# Day_light_emulate_for_birds_unrouted.net
KiCad netlist of a schematic drawn in EAGLE
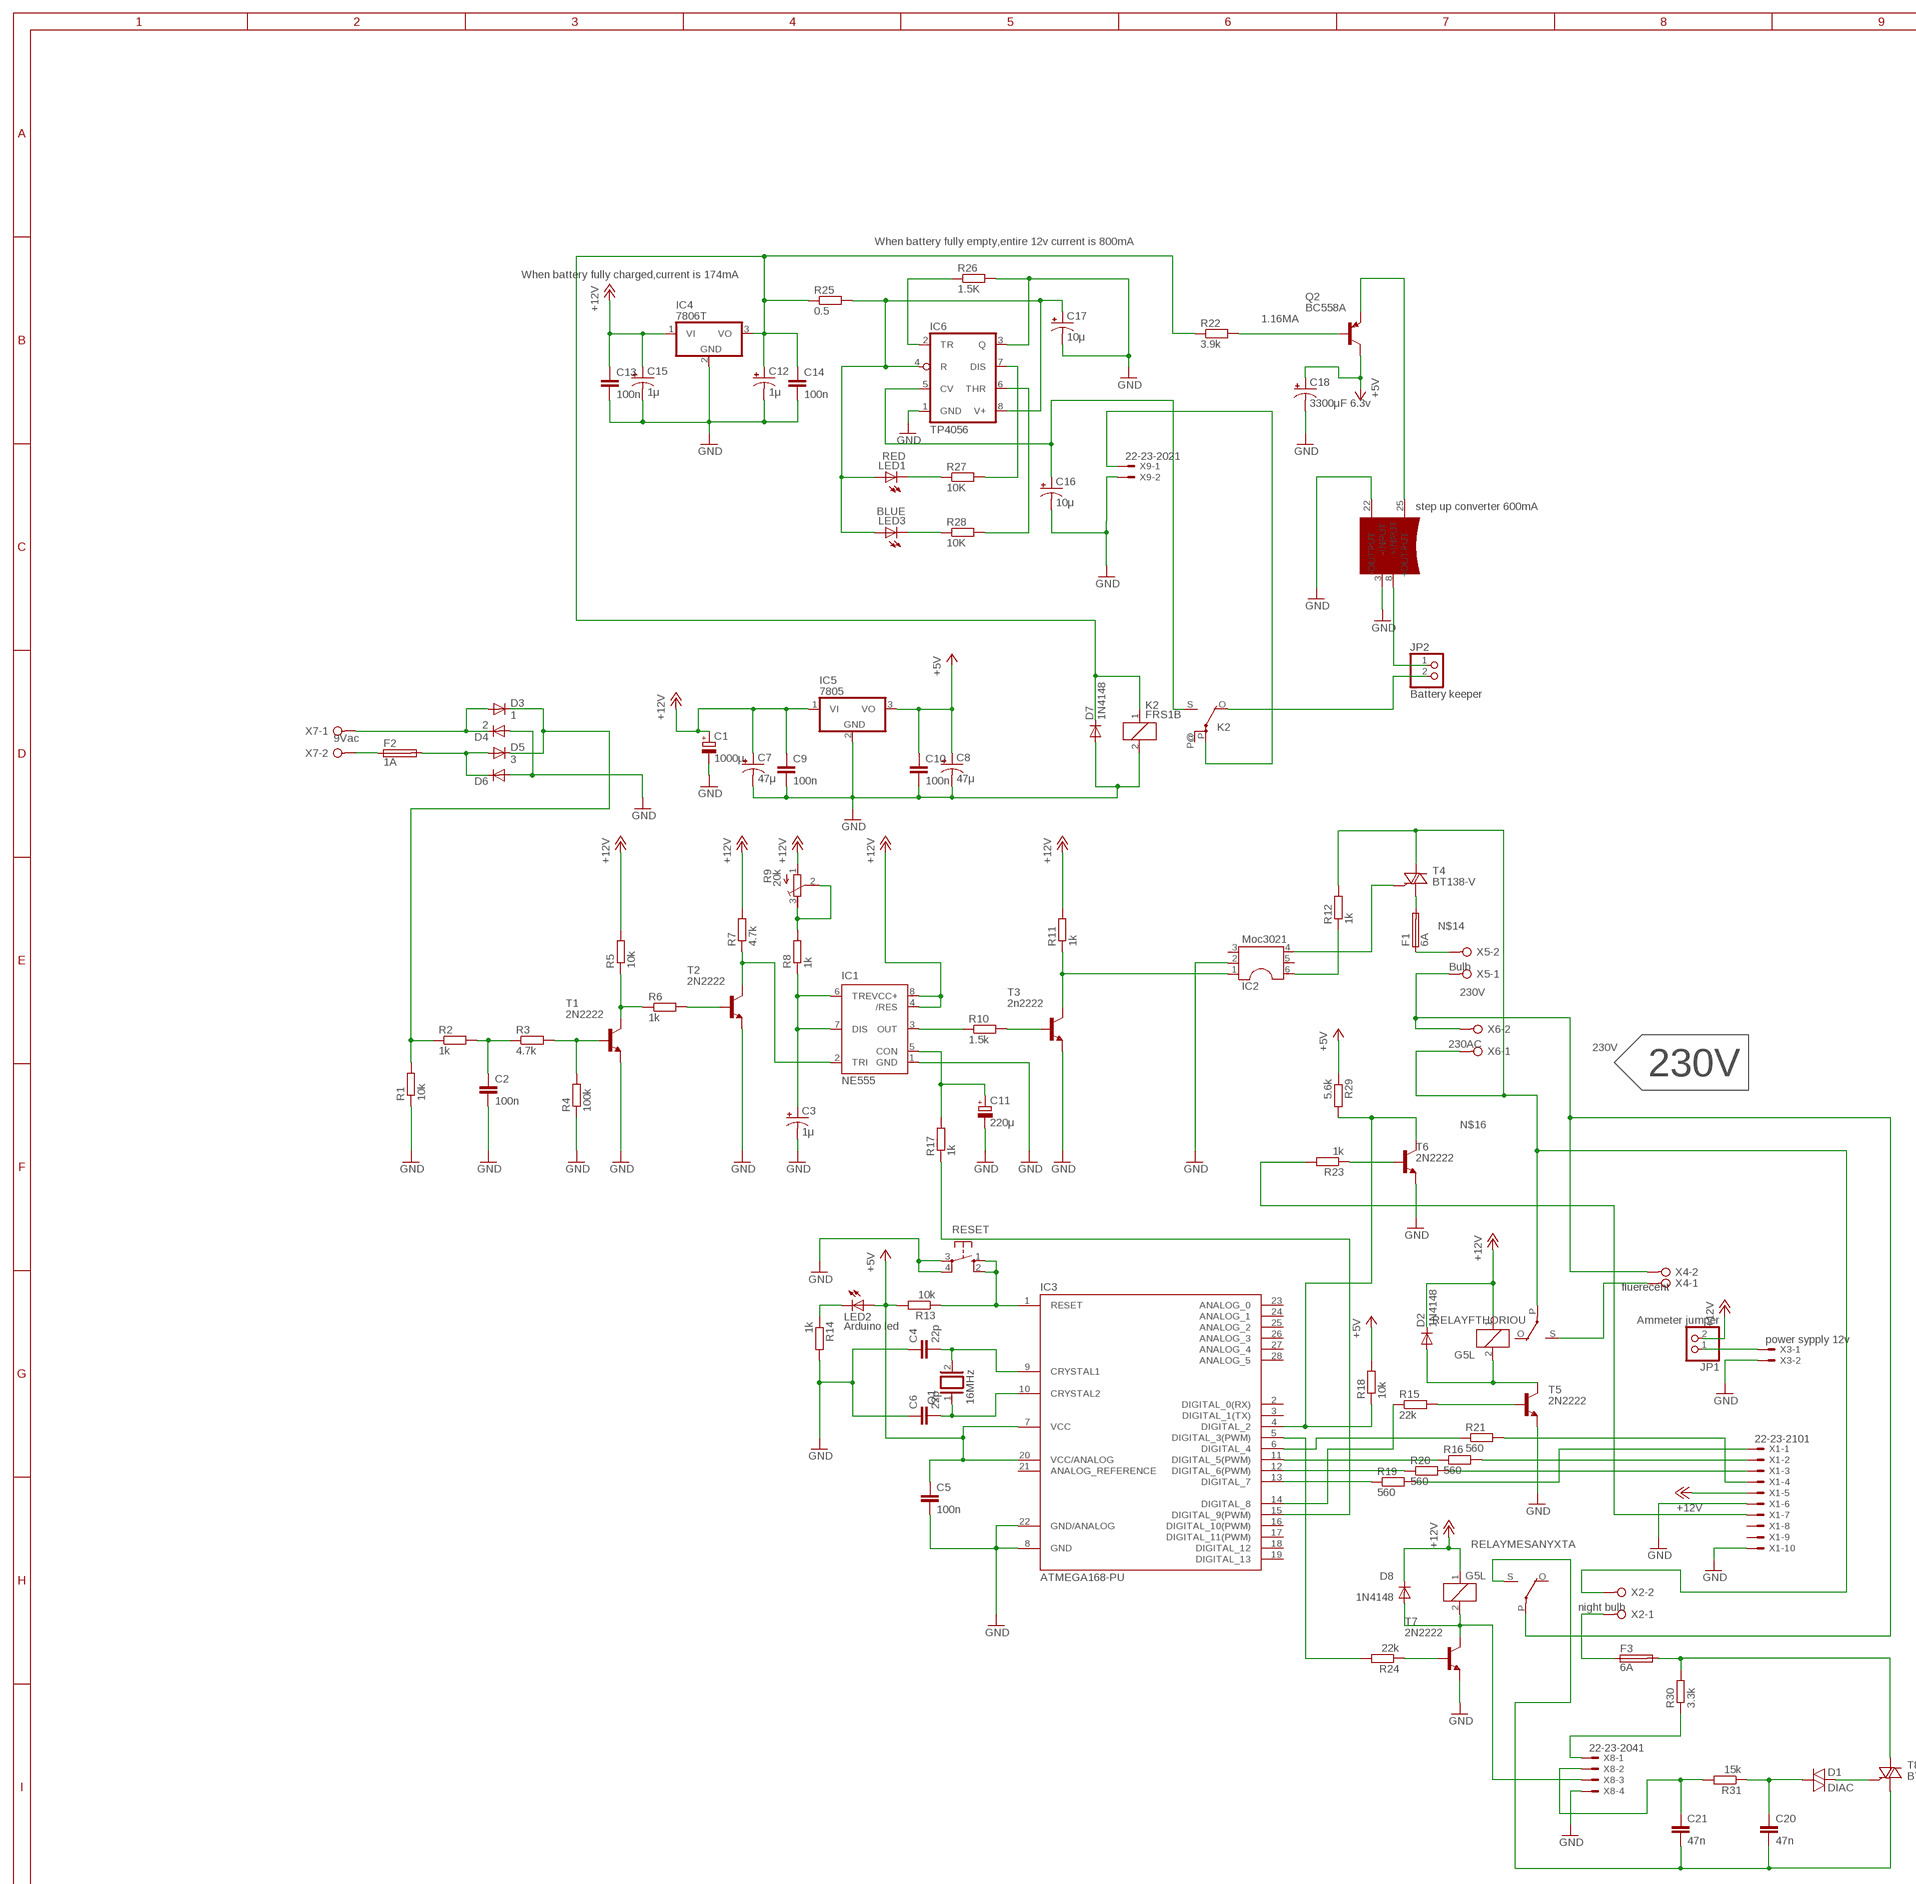
[diagram p0: schematic, sheet 1, part 1 of 2]
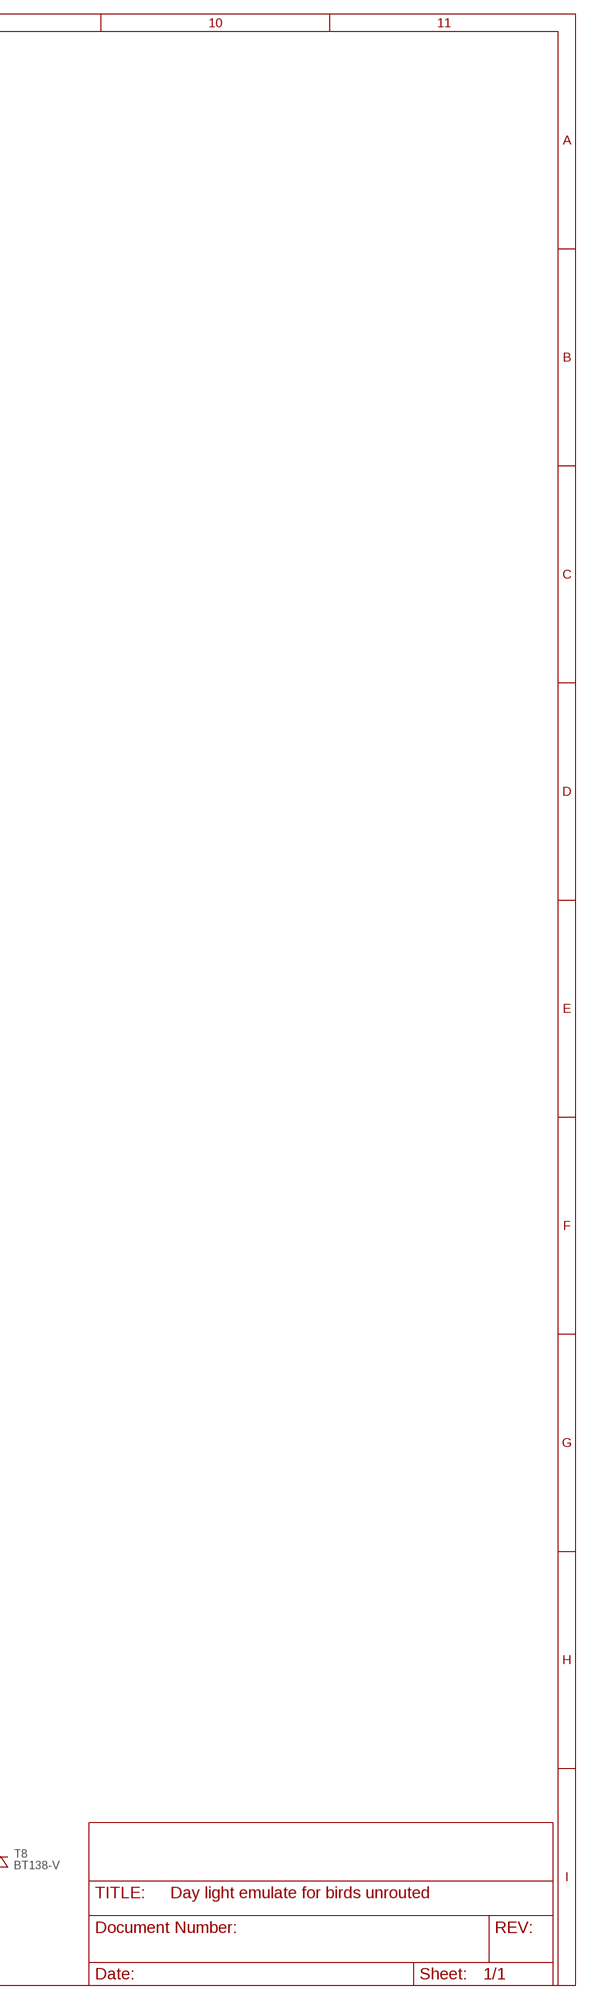
[diagram p1: schematic, sheet 1, part 2 of 2]

(export (version "E")
  (design (tool "Eeschema 10.0.6"))
  (components
    (comp (ref "C1")
      (value "1000μ")
      (footprint "eagle-import:E5-13")
      (libsource (lib "eagle-import") (part "CPOL-EUE5-13"))
    )
    (comp (ref "C2")
      (value "100n")
      (footprint "eagle-import:C025-030X050")
      (libsource (lib "eagle-import") (part "C-EU025-030X050"))
    )
    (comp (ref "C3")
      (value "1μ")
      (footprint "eagle-import:E2-4")
      (libsource (lib "eagle-import") (part "CPOL-USE2-4"))
    )
    (comp (ref "C4")
      (value "22p")
      (footprint "eagle-import:C025-030X050")
      (libsource (lib "eagle-import") (part "C-EU025-030X050"))
    )
    (comp (ref "C5")
      (value "100n")
      (footprint "eagle-import:C025-030X050")
      (libsource (lib "eagle-import") (part "C-EU025-030X050"))
    )
    (comp (ref "C6")
      (value "22p")
      (footprint "eagle-import:C025-030X050")
      (libsource (lib "eagle-import") (part "C-EU025-030X050"))
    )
    (comp (ref "C7")
      (value "47μ")
      (footprint "eagle-import:E2-4")
      (libsource (lib "eagle-import") (part "CPOL-USE2-4"))
    )
    (comp (ref "C8")
      (value "47μ")
      (footprint "eagle-import:E2-4")
      (libsource (lib "eagle-import") (part "CPOL-USE2-4"))
    )
    (comp (ref "C9")
      (value "100n")
      (footprint "eagle-import:C025-030X050")
      (libsource (lib "eagle-import") (part "C-EU025-030X050"))
    )
    (comp (ref "C10")
      (value "100n")
      (footprint "eagle-import:C025-030X050")
      (libsource (lib "eagle-import") (part "C-EU025-030X050"))
    )
    (comp (ref "C11")
      (value "220μ")
      (footprint "eagle-import:E5-10,5")
      (libsource (lib "eagle-import") (part "CPOL-EUE5-10.5"))
    )
    (comp (ref "C12")
      (value "1μ")
      (footprint "eagle-import:E2-4")
      (libsource (lib "eagle-import") (part "CPOL-USE2-4"))
    )
    (comp (ref "C13")
      (value "100n")
      (footprint "eagle-import:C025-030X050")
      (libsource (lib "eagle-import") (part "C-EU025-030X050"))
    )
    (comp (ref "C14")
      (value "100n")
      (footprint "eagle-import:C025-030X050")
      (libsource (lib "eagle-import") (part "C-EU025-030X050"))
    )
    (comp (ref "C15")
      (value "1μ")
      (footprint "eagle-import:E2-4")
      (libsource (lib "eagle-import") (part "CPOL-USE2-4"))
    )
    (comp (ref "C16")
      (value "10μ")
      (footprint "eagle-import:E2-4")
      (libsource (lib "eagle-import") (part "CPOL-USE2-4"))
    )
    (comp (ref "C17")
      (value "10μ")
      (footprint "eagle-import:E2-4")
      (libsource (lib "eagle-import") (part "CPOL-USE2-4"))
    )
    (comp (ref "C18")
      (value "3300μF 6.3v")
      (footprint "eagle-import:E5-6")
      (libsource (lib "eagle-import") (part "CPOL-USE5-6"))
    )
    (comp (ref "C20")
      (value "47n")
      (footprint "eagle-import:C025-030X050")
      (libsource (lib "eagle-import") (part "C-EU025-030X050"))
    )
    (comp (ref "C21")
      (value "47n")
      (footprint "eagle-import:C025-030X050")
      (libsource (lib "eagle-import") (part "C-EU025-030X050"))
    )
    (comp (ref "D1")
      (value "DIAC")
      (footprint "eagle-import:GT32")
      (libsource (lib "eagle-import") (part "DIAC-GT32"))
    )
    (comp (ref "D2")
      (value "1N4148")
      (footprint "eagle-import:DO35-10")
      (libsource (lib "eagle-import") (part "1N4148"))
    )
    (comp (ref "D3")
      (value "1")
      (footprint "eagle-import:DO41-10")
      (libsource (lib "eagle-import") (part "1N4004"))
    )
    (comp (ref "D4")
      (value "2")
      (footprint "eagle-import:DO41-10")
      (libsource (lib "eagle-import") (part "1N4004"))
    )
    (comp (ref "D5")
      (value "3")
      (footprint "eagle-import:DO41-10")
      (libsource (lib "eagle-import") (part "1N4004"))
    )
    (comp (ref "D6")
      (value "1N4004")
      (footprint "eagle-import:DO41-10")
      (libsource (lib "eagle-import") (part "1N4004"))
    )
    (comp (ref "D7")
      (value "1N4148")
      (footprint "eagle-import:DO35-10")
      (libsource (lib "eagle-import") (part "1N4148"))
    )
    (comp (ref "D8")
      (value "1N4148")
      (footprint "eagle-import:DO35-10")
      (libsource (lib "eagle-import") (part "1N4148"))
    )
    (comp (ref "F1")
      (value "6A")
      (footprint "eagle-import:SHK20L")
      (libsource (lib "eagle-import") (part "FUSESHK20L"))
    )
    (comp (ref "F2")
      (value "1A")
      (footprint "eagle-import:SHK20L")
      (libsource (lib "eagle-import") (part "FUSESHK20L"))
    )
    (comp (ref "F3")
      (value "6A")
      (footprint "eagle-import:SHK20L")
      (libsource (lib "eagle-import") (part "FUSESHK20L"))
    )
    (comp (ref "IC1")
      (value "NE555")
      (footprint "eagle-import:DIL-08")
      (libsource (lib "eagle-import") (part "NE555"))
    )
    (comp (ref "IC2")
      (value "Moc3021")
      (footprint "eagle-import:DIL06")
      (libsource (lib "eagle-import") (part "DIL6"))
    )
    (comp (ref "IC3")
      (value "ATMEGA168-PU")
      (footprint "eagle-import:DIL28-3")
      (libsource (lib "eagle-import") (part "ATMEGA168-PU"))
    )
    (comp (ref "IC4")
      (value "7806T")
      (footprint "eagle-import:TO220H")
      (libsource (lib "eagle-import") (part "78T06"))
    )
    (comp (ref "IC5")
      (value "7805")
      (footprint "eagle-import:TO220V")
      (libsource (lib "eagle-import") (part "78TV05"))
    )
    (comp (ref "IC6")
      (value "TP4056")
      (footprint "eagle-import:SO08")
      (libsource (lib "eagle-import") (part "555DLM"))
    )
    (comp (ref "JP1")
      (value "Ammeter jumper")
      (footprint "eagle-import:1X02")
      (libsource (lib "eagle-import") (part "PINHD-1X2"))
    )
    (comp (ref "JP2")
      (value "Battery keeper")
      (footprint "eagle-import:1X02")
      (libsource (lib "eagle-import") (part "PINHD-1X2"))
    )
    (comp (ref "K2")
      (value "FRS1B")
      (footprint "eagle-import:FRS1B")
      (libsource (lib "eagle-import") (part "FRS1B"))
    )
    (comp (ref "LED1")
      (value "RED")
      (footprint "eagle-import:LED3MM")
      (libsource (lib "eagle-import") (part "LED3MM"))
    )
    (comp (ref "LED2")
      (value "Arduino led")
      (footprint "eagle-import:LED3MM")
      (libsource (lib "eagle-import") (part "led_LED3MM"))
    )
    (comp (ref "LED3")
      (value "BLUE")
      (footprint "eagle-import:LED3MM")
      (libsource (lib "eagle-import") (part "LED3MM"))
    )
    (comp (ref "Q1")
      (value "16MHz")
      (footprint "eagle-import:QS")
      (libsource (lib "eagle-import") (part "XTAL/S"))
    )
    (comp (ref "Q2")
      (value "BC558A")
      (footprint "eagle-import:TO92-EBC")
      (libsource (lib "eagle-import") (part "BC558A"))
    )
    (comp (ref "R1")
      (value "10k")
      (footprint "eagle-import:0207_10")
      (libsource (lib "eagle-import") (part "R-EU_0207/10"))
    )
    (comp (ref "R2")
      (value "1k")
      (footprint "eagle-import:0207_10")
      (libsource (lib "eagle-import") (part "R-EU_0207/10"))
    )
    (comp (ref "R3")
      (value "4.7k")
      (footprint "eagle-import:0207_10")
      (libsource (lib "eagle-import") (part "R-EU_0207/10"))
    )
    (comp (ref "R4")
      (value "100k")
      (footprint "eagle-import:0207_10")
      (libsource (lib "eagle-import") (part "R-EU_0207/10"))
    )
    (comp (ref "R5")
      (value "10k")
      (footprint "eagle-import:0207_10")
      (libsource (lib "eagle-import") (part "R-EU_0207/10"))
    )
    (comp (ref "R6")
      (value "1k")
      (footprint "eagle-import:0207_10")
      (libsource (lib "eagle-import") (part "R-EU_0207/10"))
    )
    (comp (ref "R7")
      (value "4.7k")
      (footprint "eagle-import:0207_10")
      (libsource (lib "eagle-import") (part "R-EU_0207/10"))
    )
    (comp (ref "R8")
      (value "1k")
      (footprint "eagle-import:0207_10")
      (libsource (lib "eagle-import") (part "R-EU_0207/10"))
    )
    (comp (ref "R9")
      (value "20k")
      (footprint "eagle-import:RTRIM3339P")
      (libsource (lib "eagle-import") (part "R-TRIMM3339P"))
    )
    (comp (ref "R10")
      (value "1.5k")
      (footprint "eagle-import:0207_10")
      (libsource (lib "eagle-import") (part "R-EU_0207/10"))
    )
    (comp (ref "R11")
      (value "1k")
      (footprint "eagle-import:0207_10")
      (libsource (lib "eagle-import") (part "R-EU_0207/10"))
    )
    (comp (ref "R12")
      (value "1k")
      (footprint "eagle-import:0207_10")
      (libsource (lib "eagle-import") (part "R-EU_0207/10"))
    )
    (comp (ref "R13")
      (value "10k")
      (footprint "eagle-import:0207_10")
      (libsource (lib "eagle-import") (part "R-EU_0207/10"))
    )
    (comp (ref "R14")
      (value "1k")
      (footprint "eagle-import:0207_10")
      (libsource (lib "eagle-import") (part "R-EU_0207/10"))
    )
    (comp (ref "R15")
      (value "22k")
      (footprint "eagle-import:0207_10")
      (libsource (lib "eagle-import") (part "R-EU_0207/10"))
    )
    (comp (ref "R16")
      (value "560")
      (footprint "eagle-import:0207_10")
      (libsource (lib "eagle-import") (part "R-EU_0207/10"))
    )
    (comp (ref "R17")
      (value "1k")
      (footprint "eagle-import:0207_10")
      (libsource (lib "eagle-import") (part "R-EU_0207/10"))
    )
    (comp (ref "R18")
      (value "10k")
      (footprint "eagle-import:0207_10")
      (libsource (lib "eagle-import") (part "R-EU_0207/10"))
    )
    (comp (ref "R19")
      (value "560")
      (footprint "eagle-import:0207_10")
      (libsource (lib "eagle-import") (part "R-EU_0207/10"))
    )
    (comp (ref "R20")
      (value "560")
      (footprint "eagle-import:0207_10")
      (libsource (lib "eagle-import") (part "R-EU_0207/10"))
    )
    (comp (ref "R21")
      (value "560")
      (footprint "eagle-import:0207_10")
      (libsource (lib "eagle-import") (part "R-EU_0207/10"))
    )
    (comp (ref "R22")
      (value "3.9k")
      (footprint "eagle-import:0207_10")
      (libsource (lib "eagle-import") (part "R-EU_0207/10"))
    )
    (comp (ref "R23")
      (value "1k")
      (footprint "eagle-import:0207_10")
      (libsource (lib "eagle-import") (part "R-EU_0207/10"))
    )
    (comp (ref "R24")
      (value "22k")
      (footprint "eagle-import:0207_10")
      (libsource (lib "eagle-import") (part "R-EU_0207/10"))
    )
    (comp (ref "R25")
      (value "0.5")
      (footprint "eagle-import:0207_10")
      (libsource (lib "eagle-import") (part "R-EU_0207/10"))
    )
    (comp (ref "R26")
      (value "1.5K")
      (footprint "eagle-import:0207_10")
      (fields (field (name "CURRENT") "When battery fully empty,entire 12v current is 800mA"))
      (libsource (lib "eagle-import") (part "R-EU_0207/10"))
    )
    (comp (ref "R27")
      (value "10K")
      (footprint "eagle-import:0207_10")
      (libsource (lib "eagle-import") (part "R-EU_0207/10"))
    )
    (comp (ref "R28")
      (value "10K")
      (footprint "eagle-import:0207_10")
      (libsource (lib "eagle-import") (part "R-EU_0207/10"))
    )
    (comp (ref "R29")
      (value "5.6k")
      (footprint "eagle-import:0207_10")
      (libsource (lib "eagle-import") (part "R-EU_0207/10"))
    )
    (comp (ref "R30")
      (value "3.3k")
      (footprint "eagle-import:0207_10")
      (libsource (lib "eagle-import") (part "R-EU_0207/10"))
    )
    (comp (ref "R31")
      (value "15k")
      (footprint "eagle-import:0207_10")
      (libsource (lib "eagle-import") (part "R-EU_0207/10"))
    )
    (comp (ref "RELAYFTHORIOU")
      (value "G5L")
      (footprint "eagle-import:G5LE")
      (libsource (lib "eagle-import") (part "G5L"))
    )
    (comp (ref "RELAYMESANYXTA")
      (value "G5L")
      (footprint "eagle-import:G5LE")
      (libsource (lib "eagle-import") (part "G5L"))
    )
    (comp (ref "RESET")
      (value "10-XX")
      (footprint "eagle-import:B3F-10XX")
      (libsource (lib "eagle-import") (part "10-XX"))
    )
    (comp (ref "STEPUP1")
      (value "steup converter 600mA")
      (footprint "eagle-import:STEPUP_CONVERTER_600MA")
      (fields (field (name "STEPUP") "step up converter 600mA"))
      (libsource (lib "eagle-import") (part "STEP_UP_CONVERTER_600MA"))
    )
    (comp (ref "T1")
      (value "2N2222")
      (footprint "eagle-import:TO18")
      (libsource (lib "eagle-import") (part "2N2222"))
    )
    (comp (ref "T2")
      (value "2N2222")
      (footprint "eagle-import:TO18")
      (libsource (lib "eagle-import") (part "2N2222"))
    )
    (comp (ref "T3")
      (value "2n2222")
      (footprint "eagle-import:TO18")
      (libsource (lib "eagle-import") (part "2N2222"))
    )
    (comp (ref "T4")
      (value "BT138-V")
      (footprint "eagle-import:TO220BV")
      (libsource (lib "eagle-import") (part "BT138-V"))
    )
    (comp (ref "T5")
      (value "2N2222")
      (footprint "eagle-import:TO18")
      (libsource (lib "eagle-import") (part "2N2222"))
    )
    (comp (ref "T6")
      (value "2N2222")
      (footprint "eagle-import:TO18")
      (libsource (lib "eagle-import") (part "2N2222"))
    )
    (comp (ref "T7")
      (value "2N2222")
      (footprint "eagle-import:TO18")
      (libsource (lib "eagle-import") (part "2N2222"))
    )
    (comp (ref "T8")
      (value "BT138-V")
      (footprint "eagle-import:TO220BV")
      (libsource (lib "eagle-import") (part "BT138-V"))
    )
    (comp (ref "X1")
      (value "22-23-2101")
      (footprint "eagle-import:22-23-2101")
      (libsource (lib "eagle-import") (part "22-23-2101"))
    )
    (comp (ref "X2")
      (value "night bulb")
      (footprint "eagle-import:W237-132")
      (libsource (lib "eagle-import") (part "W237-02P"))
    )
    (comp (ref "X3")
      (value "power sypply 12v")
      (footprint "eagle-import:22-23-2021")
      (libsource (lib "eagle-import") (part "22-23-2021"))
    )
    (comp (ref "X4")
      (value "fluerecent")
      (footprint "eagle-import:W237-132")
      (libsource (lib "eagle-import") (part "W237-02P"))
    )
    (comp (ref "X5")
      (value "Bulb")
      (footprint "eagle-import:W237-132")
      (libsource (lib "eagle-import") (part "W237-02P"))
    )
    (comp (ref "X6")
      (value "230AC")
      (footprint "eagle-import:W237-132")
      (libsource (lib "eagle-import") (part "W237-02P"))
    )
    (comp (ref "X7")
      (value "9Vac")
      (footprint "eagle-import:W237-132")
      (libsource (lib "eagle-import") (part "W237-02P"))
    )
    (comp (ref "X8")
      (value "22-23-2041")
      (footprint "eagle-import:22-23-2041")
      (libsource (lib "eagle-import") (part "22-23-2041"))
    )
    (comp (ref "X9")
      (value "22-23-2021")
      (footprint "eagle-import:22-23-2021")
      (libsource (lib "eagle-import") (part "22-23-2021"))
    )
  )
  (nets
    (net (code "1") (name "+5V") (class "Default")
      (node (ref "C10") (pin "1") (pinfunction "1_1") (pintype "passive"))
      (node (ref "C18") (pin "+") (pinfunction "+_+") (pintype "passive"))
      (node (ref "C5") (pin "1") (pinfunction "1_1") (pintype "passive"))
      (node (ref "C8") (pin "+") (pinfunction "+_+") (pintype "passive"))
      (node (ref "IC3") (pin "20") (pinfunction "VCC/ANALOG_20") (pintype "passive"))
      (node (ref "IC3") (pin "7") (pinfunction "VCC_7") (pintype "power_in"))
      (node (ref "IC5") (pin "3") (pinfunction "VO_3") (pintype "passive"))
      (node (ref "LED2") (pin "A") (pinfunction "A_A") (pintype "passive"))
      (node (ref "Q2") (pin "C") (pinfunction "C_C") (pintype "passive"))
      (node (ref "R13") (pin "2") (pinfunction "2_2") (pintype "passive"))
      (node (ref "R18") (pin "2") (pinfunction "2_2") (pintype "passive"))
      (node (ref "R29") (pin "1") (pinfunction "1_1") (pintype "passive"))
    )
    (net (code "2") (name "+12V") (class "Default")
      (node (ref "C1") (pin "+") (pinfunction "+_+") (pintype "passive"))
      (node (ref "C13") (pin "1") (pinfunction "1_1") (pintype "passive"))
      (node (ref "C15") (pin "+") (pinfunction "+_+") (pintype "passive"))
      (node (ref "C7") (pin "+") (pinfunction "+_+") (pintype "passive"))
      (node (ref "C9") (pin "1") (pinfunction "1_1") (pintype "passive"))
      (node (ref "D2") (pin "C") (pinfunction "C_C") (pintype "passive"))
      (node (ref "D8") (pin "C") (pinfunction "C_C") (pintype "passive"))
      (node (ref "IC1") (pin "4") (pinfunction "/RES_4") (pintype "input"))
      (node (ref "IC1") (pin "8") (pinfunction "VCC+_8") (pintype "power_in"))
      (node (ref "IC4") (pin "1") (pinfunction "VI_1") (pintype "input"))
      (node (ref "IC5") (pin "1") (pinfunction "VI_1") (pintype "input"))
      (node (ref "JP1") (pin "2") (pinfunction "2_2") (pintype "passive"))
      (node (ref "R11") (pin "2") (pinfunction "2_2") (pintype "passive"))
      (node (ref "R5") (pin "2") (pinfunction "2_2") (pintype "passive"))
      (node (ref "R7") (pin "2") (pinfunction "2_2") (pintype "passive"))
      (node (ref "R9") (pin "1") (pinfunction "E_1") (pintype "passive"))
      (node (ref "RELAYFTHORIOU") (pin "1") (pinfunction "1_1") (pintype "passive"))
      (node (ref "RELAYMESANYXTA") (pin "1") (pinfunction "1_1") (pintype "passive"))
      (node (ref "X1") (pin "5") (pinfunction "S_5") (pintype "passive"))
    )
    (net (code "3") (name "/1.16MA") (class "Default")
      (node (ref "Q2") (pin "B") (pinfunction "B_B") (pintype "passive"))
      (node (ref "R22") (pin "2") (pinfunction "2_2") (pintype "passive"))
    )
    (net (code "4") (name "/N$14") (class "Default")
      (node (ref "F1") (pin "1A") (pinfunction "1_1A") (pintype "passive"))
      (node (ref "X5") (pin "2") (pinfunction "KL_2") (pintype "passive"))
    )
    (net (code "5") (name "/N$16") (class "Default")
      (node (ref "R12") (pin "2") (pinfunction "2_2") (pintype "passive"))
      (node (ref "RELAYFTHORIOU") (pin "P") (pinfunction "P_P") (pintype "passive"))
      (node (ref "T4") (pin "T2") (pinfunction "A2_T2") (pintype "passive"))
      (node (ref "X2") (pin "2") (pinfunction "KL_2") (pintype "passive"))
      (node (ref "X6") (pin "1") (pinfunction "KL_1") (pintype "passive"))
    )
    (net (code "6") (name "230V") (class "Default")
      (node (ref "RELAYMESANYXTA") (pin "P") (pinfunction "P_P") (pintype "passive"))
      (node (ref "X4") (pin "2") (pinfunction "KL_2") (pintype "passive"))
      (node (ref "X5") (pin "1") (pinfunction "KL_1") (pintype "passive"))
      (node (ref "X6") (pin "2") (pinfunction "KL_2") (pintype "passive"))
    )
    (net (code "7") (name "GND") (class "Default")
      (node (ref "C1") (pin "-") (pinfunction "-_-") (pintype "passive"))
      (node (ref "C10") (pin "2") (pinfunction "2_2") (pintype "passive"))
      (node (ref "C11") (pin "-") (pinfunction "-_-") (pintype "passive"))
      (node (ref "C12") (pin "-") (pinfunction "-_-") (pintype "passive"))
      (node (ref "C13") (pin "2") (pinfunction "2_2") (pintype "passive"))
      (node (ref "C14") (pin "2") (pinfunction "2_2") (pintype "passive"))
      (node (ref "C15") (pin "-") (pinfunction "-_-") (pintype "passive"))
      (node (ref "C16") (pin "-") (pinfunction "-_-") (pintype "passive"))
      (node (ref "C17") (pin "-") (pinfunction "-_-") (pintype "passive"))
      (node (ref "C18") (pin "-") (pinfunction "-_-") (pintype "passive"))
      (node (ref "C2") (pin "2") (pinfunction "2_2") (pintype "passive"))
      (node (ref "C3") (pin "-") (pinfunction "-_-") (pintype "passive"))
      (node (ref "C4") (pin "1") (pinfunction "1_1") (pintype "passive"))
      (node (ref "C5") (pin "2") (pinfunction "2_2") (pintype "passive"))
      (node (ref "C6") (pin "1") (pinfunction "1_1") (pintype "passive"))
      (node (ref "C7") (pin "-") (pinfunction "-_-") (pintype "passive"))
      (node (ref "C8") (pin "-") (pinfunction "-_-") (pintype "passive"))
      (node (ref "C9") (pin "2") (pinfunction "2_2") (pintype "passive"))
      (node (ref "D4") (pin "A") (pinfunction "A_A") (pintype "passive"))
      (node (ref "D6") (pin "A") (pinfunction "A_A") (pintype "passive"))
      (node (ref "D7") (pin "A") (pinfunction "A_A") (pintype "passive"))
      (node (ref "IC1") (pin "1") (pinfunction "GND_1") (pintype "power_in"))
      (node (ref "IC2") (pin "2") (pinfunction "2_2") (pintype "passive"))
      (node (ref "IC3") (pin "22") (pinfunction "GND/ANALOG_22") (pintype "power_in"))
      (node (ref "IC3") (pin "8") (pinfunction "GND_8") (pintype "power_in"))
      (node (ref "IC4") (pin "2") (pinfunction "GND_2") (pintype "passive"))
      (node (ref "IC5") (pin "2") (pinfunction "GND_2") (pintype "passive"))
      (node (ref "IC6") (pin "1") (pinfunction "GND_1") (pintype "power_in"))
      (node (ref "IC6") (pin "3") (pinfunction "Q_3") (pintype "output"))
      (node (ref "K2") (pin "2") (pinfunction "2_2") (pintype "passive"))
      (node (ref "R1") (pin "1") (pinfunction "1_1") (pintype "passive"))
      (node (ref "R14") (pin "2") (pinfunction "2_2") (pintype "passive"))
      (node (ref "R26") (pin "2") (pinfunction "2_2") (pintype "passive"))
      (node (ref "R4") (pin "1") (pinfunction "1_1") (pintype "passive"))
      (node (ref "RESET") (pin "3") (pinfunction "P_3") (pintype "passive"))
      (node (ref "RESET") (pin "4") (pinfunction "P1_4") (pintype "passive"))
      (node (ref "STEPUP1") (pin "22") (pinfunction "-OUTPUT_22") (pintype "bidirectional"))
      (node (ref "STEPUP1") (pin "3") (pinfunction "-INPUT_3") (pintype "bidirectional"))
      (node (ref "T1") (pin "1") (pinfunction "E_1") (pintype "passive"))
      (node (ref "T2") (pin "1") (pinfunction "E_1") (pintype "passive"))
      (node (ref "T3") (pin "1") (pinfunction "E_1") (pintype "passive"))
      (node (ref "T5") (pin "1") (pinfunction "E_1") (pintype "passive"))
      (node (ref "T6") (pin "1") (pinfunction "E_1") (pintype "passive"))
      (node (ref "T7") (pin "1") (pinfunction "E_1") (pintype "passive"))
      (node (ref "X1") (pin "10") (pinfunction "S_10") (pintype "passive"))
      (node (ref "X1") (pin "6") (pinfunction "S_6") (pintype "passive"))
      (node (ref "X3") (pin "2") (pinfunction "S_2") (pintype "passive"))
      (node (ref "X8") (pin "4") (pinfunction "S_4") (pintype "passive"))
      (node (ref "X9") (pin "2") (pinfunction "S_2") (pintype "passive"))
    )
    (net (code "8") (name "Net-(C2-Pad1)") (class "Default")
      (node (ref "C2") (pin "1") (pinfunction "1_1") (pintype "passive"))
      (node (ref "R2") (pin "2") (pinfunction "2_2") (pintype "passive"))
      (node (ref "R3") (pin "1") (pinfunction "1_1") (pintype "passive"))
    )
    (net (code "9") (name "Net-(C20-Pad1)") (class "Default")
      (node (ref "C20") (pin "1") (pinfunction "1_1") (pintype "passive"))
      (node (ref "D1") (pin "1") (pinfunction "1_1") (pintype "passive"))
      (node (ref "R31") (pin "1") (pinfunction "1_1") (pintype "passive"))
    )
    (net (code "10") (name "Net-(D1-Pad2)") (class "Default")
      (node (ref "D1") (pin "2") (pinfunction "2_2") (pintype "passive"))
      (node (ref "T8") (pin "G") (pinfunction "G_G") (pintype "passive"))
    )
    (net (code "11") (name "Net-(D3-PadC)") (class "Default")
      (node (ref "D3") (pin "C") (pinfunction "C_C") (pintype "passive"))
      (node (ref "D5") (pin "C") (pinfunction "C_C") (pintype "passive"))
      (node (ref "R1") (pin "2") (pinfunction "2_2") (pintype "passive"))
      (node (ref "R2") (pin "1") (pinfunction "1_1") (pintype "passive"))
    )
    (net (code "12") (name "Net-(F1-2)") (class "Default")
      (node (ref "F1") (pin "2A") (pinfunction "2_2A") (pintype "passive"))
      (node (ref "T4") (pin "T1") (pinfunction "A1_T1") (pintype "passive"))
    )
    (net (code "13") (name "Net-(F2-1)") (class "Default")
      (node (ref "F2") (pin "1A") (pinfunction "1_1A") (pintype "passive"))
      (node (ref "X7") (pin "2") (pinfunction "KL_2") (pintype "passive"))
    )
    (net (code "14") (name "Net-(F2-2)") (class "Default")
      (node (ref "D5") (pin "A") (pinfunction "A_A") (pintype "passive"))
      (node (ref "D6") (pin "C") (pinfunction "C_C") (pintype "passive"))
      (node (ref "F2") (pin "2A") (pinfunction "2_2A") (pintype "passive"))
    )
    (net (code "15") (name "Net-(F3-1)") (class "Default")
      (node (ref "F3") (pin "1A") (pinfunction "1_1A") (pintype "passive"))
      (node (ref "X2") (pin "1") (pinfunction "KL_1") (pintype "passive"))
    )
    (net (code "16") (name "Net-(F3-2)") (class "Default")
      (node (ref "F3") (pin "2A") (pinfunction "2_2A") (pintype "passive"))
      (node (ref "R30") (pin "2") (pinfunction "2_2") (pintype "passive"))
      (node (ref "T8") (pin "T2") (pinfunction "A2_T2") (pintype "passive"))
    )
    (net (code "17") (name "Net-(IC1-CON)") (class "Default")
      (node (ref "C11") (pin "+") (pinfunction "+_+") (pintype "passive"))
      (node (ref "IC1") (pin "5") (pinfunction "CON_5") (pintype "input"))
      (node (ref "R17") (pin "2") (pinfunction "2_2") (pintype "passive"))
    )
    (net (code "18") (name "Net-(IC1-DIS)") (class "Default")
      (node (ref "C3") (pin "+") (pinfunction "+_+") (pintype "passive"))
      (node (ref "IC1") (pin "6") (pinfunction "TRE_6") (pintype "input"))
      (node (ref "IC1") (pin "7") (pinfunction "DIS_7") (pintype "input"))
      (node (ref "R8") (pin "1") (pinfunction "1_1") (pintype "passive"))
    )
    (net (code "19") (name "Net-(IC1-OUT)") (class "Default")
      (node (ref "IC1") (pin "3") (pinfunction "OUT_3") (pintype "output"))
      (node (ref "R10") (pin "1") (pinfunction "1_1") (pintype "passive"))
    )
    (net (code "20") (name "Net-(IC1-TRI)") (class "Default")
      (node (ref "IC1") (pin "2") (pinfunction "TRI_2") (pintype "input"))
      (node (ref "R7") (pin "1") (pinfunction "1_1") (pintype "passive"))
      (node (ref "T2") (pin "3") (pinfunction "C_3") (pintype "passive"))
    )
    (net (code "21") (name "Net-(IC2-Pad4)") (class "Default")
      (node (ref "IC2") (pin "4") (pinfunction "4_4") (pintype "passive"))
      (node (ref "T4") (pin "G") (pinfunction "G_G") (pintype "passive"))
    )
    (net (code "22") (name "Net-(IC2-Pad6)") (class "Default")
      (node (ref "IC2") (pin "6") (pinfunction "6_6") (pintype "passive"))
      (node (ref "R12") (pin "1") (pinfunction "1_1") (pintype "passive"))
    )
    (net (code "23") (name "Net-(IC3-CRYSTAL1)") (class "Default")
      (node (ref "C4") (pin "2") (pinfunction "2_2") (pintype "passive"))
      (node (ref "IC3") (pin "9") (pinfunction "CRYSTAL1_9") (pintype "bidirectional"))
      (node (ref "Q1") (pin "2") (pinfunction "2_2") (pintype "passive"))
    )
    (net (code "24") (name "Net-(IC3-CRYSTAL2)") (class "Default")
      (node (ref "C6") (pin "2") (pinfunction "2_2") (pintype "passive"))
      (node (ref "IC3") (pin "10") (pinfunction "CRYSTAL2_10") (pintype "bidirectional"))
      (node (ref "Q1") (pin "1") (pinfunction "1_1") (pintype "passive"))
    )
    (net (code "25") (name "Net-(IC3-DIGITAL_2)") (class "Default")
      (node (ref "IC3") (pin "4") (pinfunction "DIGITAL_2_4") (pintype "bidirectional"))
      (node (ref "R18") (pin "1") (pinfunction "1_1") (pintype "passive"))
      (node (ref "R29") (pin "2") (pinfunction "2_2") (pintype "passive"))
      (node (ref "T6") (pin "3") (pinfunction "C_3") (pintype "passive"))
    )
    (net (code "26") (name "Net-(IC3-DIGITAL_3(PWM))") (class "Default")
      (node (ref "IC3") (pin "5") (pinfunction "DIGITAL_3(PWM)_5") (pintype "bidirectional"))
      (node (ref "R24") (pin "2") (pinfunction "2_2") (pintype "passive"))
    )
    (net (code "27") (name "Net-(IC3-DIGITAL_4)") (class "Default")
      (node (ref "IC3") (pin "6") (pinfunction "DIGITAL_4_6") (pintype "bidirectional"))
      (node (ref "R21") (pin "1") (pinfunction "1_1") (pintype "passive"))
    )
    (net (code "28") (name "Net-(IC3-DIGITAL_5(PWM))") (class "Default")
      (node (ref "IC3") (pin "11") (pinfunction "DIGITAL_5(PWM)_11") (pintype "bidirectional"))
      (node (ref "R16") (pin "1") (pinfunction "1_1") (pintype "passive"))
    )
    (net (code "29") (name "Net-(IC3-DIGITAL_6(PWM))") (class "Default")
      (node (ref "IC3") (pin "12") (pinfunction "DIGITAL_6(PWM)_12") (pintype "bidirectional"))
      (node (ref "R20") (pin "1") (pinfunction "1_1") (pintype "passive"))
    )
    (net (code "30") (name "Net-(IC3-DIGITAL_7)") (class "Default")
      (node (ref "IC3") (pin "13") (pinfunction "DIGITAL_7_13") (pintype "bidirectional"))
      (node (ref "R19") (pin "1") (pinfunction "1_1") (pintype "passive"))
    )
    (net (code "31") (name "Net-(IC3-DIGITAL_8)") (class "Default")
      (node (ref "IC3") (pin "14") (pinfunction "DIGITAL_8_14") (pintype "bidirectional"))
      (node (ref "R15") (pin "1") (pinfunction "1_1") (pintype "passive"))
    )
    (net (code "32") (name "Net-(IC3-DIGITAL_9(PWM))") (class "Default")
      (node (ref "IC3") (pin "15") (pinfunction "DIGITAL_9(PWM)_15") (pintype "bidirectional"))
      (node (ref "R17") (pin "1") (pinfunction "1_1") (pintype "passive"))
    )
    (net (code "33") (name "Net-(IC3-RESET)") (class "Default")
      (node (ref "IC3") (pin "1") (pinfunction "RESET_1") (pintype "bidirectional"))
      (node (ref "R13") (pin "1") (pinfunction "1_1") (pintype "passive"))
      (node (ref "RESET") (pin "1") (pinfunction "S_1") (pintype "passive"))
      (node (ref "RESET") (pin "2") (pinfunction "S1_2") (pintype "passive"))
    )
    (net (code "34") (name "Net-(IC4-VO)") (class "Default")
      (node (ref "C12") (pin "+") (pinfunction "+_+") (pintype "passive"))
      (node (ref "C14") (pin "1") (pinfunction "1_1") (pintype "passive"))
      (node (ref "D7") (pin "C") (pinfunction "C_C") (pintype "passive"))
      (node (ref "IC4") (pin "3") (pinfunction "VO_3") (pintype "passive"))
      (node (ref "K2") (pin "1") (pinfunction "1_1") (pintype "passive"))
      (node (ref "R22") (pin "1") (pinfunction "1_1") (pintype "passive"))
      (node (ref "R25") (pin "1") (pinfunction "1_1") (pintype "passive"))
    )
    (net (code "35") (name "Net-(IC6-CV)") (class "Default")
      (node (ref "C16") (pin "+") (pinfunction "+_+") (pintype "passive"))
      (node (ref "IC6") (pin "5") (pinfunction "CV_5") (pintype "input"))
      (node (ref "K2") (pin "S") (pinfunction "S_S") (pintype "passive"))
    )
    (net (code "36") (name "Net-(IC6-DIS)") (class "Default")
      (node (ref "IC6") (pin "7") (pinfunction "DIS_7") (pintype "input"))
      (node (ref "R27") (pin "2") (pinfunction "2_2") (pintype "passive"))
    )
    (net (code "37") (name "Net-(IC6-R)") (class "Default")
      (node (ref "C17") (pin "+") (pinfunction "+_+") (pintype "passive"))
      (node (ref "IC6") (pin "4") (pinfunction "R_4") (pintype "input"))
      (node (ref "IC6") (pin "8") (pinfunction "V+_8") (pintype "power_in"))
      (node (ref "LED1") (pin "A") (pinfunction "A_A") (pintype "passive"))
      (node (ref "LED3") (pin "A") (pinfunction "A_A") (pintype "passive"))
      (node (ref "R25") (pin "2") (pinfunction "2_2") (pintype "passive"))
    )
    (net (code "38") (name "Net-(IC6-THR)") (class "Default")
      (node (ref "IC6") (pin "6") (pinfunction "THR_6") (pintype "input"))
      (node (ref "R28") (pin "2") (pinfunction "2_2") (pintype "passive"))
    )
    (net (code "39") (name "Net-(IC6-TR)") (class "Default")
      (node (ref "IC6") (pin "2") (pinfunction "TR_2") (pintype "input"))
      (node (ref "R26") (pin "1") (pinfunction "1_1") (pintype "passive"))
    )
    (net (code "40") (name "Net-(JP2-Pad2)") (class "Default")
      (node (ref "JP2") (pin "2") (pinfunction "2_2") (pintype "passive"))
      (node (ref "K2") (pin "O") (pinfunction "O_O") (pintype "passive"))
    )
    (net (code "41") (name "Net-(LED1-C)") (class "Default")
      (node (ref "LED1") (pin "K") (pinfunction "C_K") (pintype "passive"))
      (node (ref "R27") (pin "1") (pinfunction "1_1") (pintype "passive"))
    )
    (net (code "42") (name "Net-(LED2-C)") (class "Default")
      (node (ref "LED2") (pin "K") (pinfunction "C_K") (pintype "passive"))
      (node (ref "R14") (pin "1") (pinfunction "1_1") (pintype "passive"))
    )
    (net (code "43") (name "Net-(LED3-C)") (class "Default")
      (node (ref "LED3") (pin "K") (pinfunction "C_K") (pintype "passive"))
      (node (ref "R28") (pin "1") (pinfunction "1_1") (pintype "passive"))
    )
    (net (code "44") (name "Net-(R9-A)") (class "Default")
      (node (ref "R8") (pin "2") (pinfunction "2_2") (pintype "passive"))
      (node (ref "R9") (pin "2") (pinfunction "S_2") (pintype "passive"))
      (node (ref "R9") (pin "3") (pinfunction "A_3") (pintype "passive"))
    )
    (net (code "45") (name "Net-(STEPUP1-+INPUT)") (class "Default")
      (node (ref "JP2") (pin "1") (pinfunction "1_1") (pintype "passive"))
      (node (ref "STEPUP1") (pin "8") (pinfunction "+INPUT_8") (pintype "bidirectional"))
    )
    (net (code "46") (name "Net-(STEPUP1-+OUTPUT)") (class "Default")
      (node (ref "Q2") (pin "E") (pinfunction "E_E") (pintype "passive"))
      (node (ref "STEPUP1") (pin "25") (pinfunction "+OUTPUT_25") (pintype "bidirectional"))
    )
    (net (code "47") (name "Net-(T1-B)") (class "Default")
      (node (ref "R3") (pin "2") (pinfunction "2_2") (pintype "passive"))
      (node (ref "R4") (pin "2") (pinfunction "2_2") (pintype "passive"))
      (node (ref "T1") (pin "2") (pinfunction "B_2") (pintype "passive"))
    )
    (net (code "48") (name "Net-(T1-C)") (class "Default")
      (node (ref "R5") (pin "1") (pinfunction "1_1") (pintype "passive"))
      (node (ref "R6") (pin "1") (pinfunction "1_1") (pintype "passive"))
      (node (ref "T1") (pin "3") (pinfunction "C_3") (pintype "passive"))
    )
    (net (code "49") (name "Net-(T2-B)") (class "Default")
      (node (ref "R6") (pin "2") (pinfunction "2_2") (pintype "passive"))
      (node (ref "T2") (pin "2") (pinfunction "B_2") (pintype "passive"))
    )
    (net (code "50") (name "Net-(T3-B)") (class "Default")
      (node (ref "R10") (pin "2") (pinfunction "2_2") (pintype "passive"))
      (node (ref "T3") (pin "2") (pinfunction "B_2") (pintype "passive"))
    )
    (net (code "51") (name "Net-(T3-C)") (class "Default")
      (node (ref "IC2") (pin "1") (pinfunction "1_1") (pintype "passive"))
      (node (ref "R11") (pin "1") (pinfunction "1_1") (pintype "passive"))
      (node (ref "T3") (pin "3") (pinfunction "C_3") (pintype "passive"))
    )
    (net (code "52") (name "Net-(T5-B)") (class "Default")
      (node (ref "R15") (pin "2") (pinfunction "2_2") (pintype "passive"))
      (node (ref "T5") (pin "2") (pinfunction "B_2") (pintype "passive"))
    )
    (net (code "53") (name "Net-(T5-C)") (class "Default")
      (node (ref "D2") (pin "A") (pinfunction "A_A") (pintype "passive"))
      (node (ref "RELAYFTHORIOU") (pin "2") (pinfunction "2_2") (pintype "passive"))
      (node (ref "T5") (pin "3") (pinfunction "C_3") (pintype "passive"))
    )
    (net (code "54") (name "Net-(T6-B)") (class "Default")
      (node (ref "R23") (pin "1") (pinfunction "1_1") (pintype "passive"))
      (node (ref "T6") (pin "2") (pinfunction "B_2") (pintype "passive"))
    )
    (net (code "55") (name "Net-(T7-B)") (class "Default")
      (node (ref "R24") (pin "1") (pinfunction "1_1") (pintype "passive"))
      (node (ref "T7") (pin "2") (pinfunction "B_2") (pintype "passive"))
    )
    (net (code "56") (name "Net-(T7-C)") (class "Default")
      (node (ref "D8") (pin "A") (pinfunction "A_A") (pintype "passive"))
      (node (ref "RELAYMESANYXTA") (pin "2") (pinfunction "2_2") (pintype "passive"))
      (node (ref "T7") (pin "3") (pinfunction "C_3") (pintype "passive"))
      (node (ref "X8") (pin "3") (pinfunction "S_3") (pintype "passive"))
    )
    (net (code "57") (name "Net-(T8-A1)") (class "Default")
      (node (ref "C20") (pin "2") (pinfunction "2_2") (pintype "passive"))
      (node (ref "C21") (pin "2") (pinfunction "2_2") (pintype "passive"))
      (node (ref "RELAYMESANYXTA") (pin "S") (pinfunction "S_S") (pintype "passive"))
      (node (ref "T8") (pin "T1") (pinfunction "A1_T1") (pintype "passive"))
    )
    (net (code "58") (name "Net-(X1A-S)") (class "Default")
      (node (ref "R19") (pin "2") (pinfunction "2_2") (pintype "passive"))
      (node (ref "X1") (pin "1") (pinfunction "S_1") (pintype "passive"))
    )
    (net (code "59") (name "Net-(X1C-S)") (class "Default")
      (node (ref "R16") (pin "2") (pinfunction "2_2") (pintype "passive"))
      (node (ref "X1") (pin "2") (pinfunction "S_2") (pintype "passive"))
    )
    (net (code "60") (name "Net-(X1D-S)") (class "Default")
      (node (ref "R20") (pin "2") (pinfunction "2_2") (pintype "passive"))
      (node (ref "X1") (pin "3") (pinfunction "S_3") (pintype "passive"))
    )
    (net (code "61") (name "Net-(X1E-S)") (class "Default")
      (node (ref "R21") (pin "2") (pinfunction "2_2") (pintype "passive"))
      (node (ref "X1") (pin "4") (pinfunction "S_4") (pintype "passive"))
    )
    (net (code "62") (name "Net-(X1H-S)") (class "Default")
      (node (ref "R23") (pin "2") (pinfunction "2_2") (pintype "passive"))
      (node (ref "X1") (pin "7") (pinfunction "S_7") (pintype "passive"))
    )
    (net (code "63") (name "Net-(X3A-S)") (class "Default")
      (node (ref "JP1") (pin "1") (pinfunction "1_1") (pintype "passive"))
      (node (ref "X3") (pin "1") (pinfunction "S_1") (pintype "passive"))
    )
    (net (code "64") (name "Net-(X4A-KL)") (class "Default")
      (node (ref "RELAYFTHORIOU") (pin "S") (pinfunction "S_S") (pintype "passive"))
      (node (ref "X4") (pin "1") (pinfunction "KL_1") (pintype "passive"))
    )
    (net (code "65") (name "Net-(X7A-KL)") (class "Default")
      (node (ref "D3") (pin "A") (pinfunction "A_A") (pintype "passive"))
      (node (ref "D4") (pin "C") (pinfunction "C_C") (pintype "passive"))
      (node (ref "X7") (pin "1") (pinfunction "KL_1") (pintype "passive"))
    )
    (net (code "66") (name "Net-(X8A-S)") (class "Default")
      (node (ref "R30") (pin "1") (pinfunction "1_1") (pintype "passive"))
      (node (ref "X8") (pin "1") (pinfunction "S_1") (pintype "passive"))
    )
    (net (code "67") (name "Net-(X8B-S)") (class "Default")
      (node (ref "C21") (pin "1") (pinfunction "1_1") (pintype "passive"))
      (node (ref "R31") (pin "2") (pinfunction "2_2") (pintype "passive"))
      (node (ref "X8") (pin "2") (pinfunction "S_2") (pintype "passive"))
    )
    (net (code "68") (name "Net-(X9A-S)") (class "Default")
      (node (ref "K2") (pin "P") (pinfunction "P_P") (pintype "passive"))
      (node (ref "X9") (pin "1") (pinfunction "S_1") (pintype "passive"))
    )
    (net (code "69") (name "unconnected-(IC2-Pad3)") (class "Default")
      (node (ref "IC2") (pin "3") (pinfunction "3_3") (pintype "passive"))
    )
    (net (code "70") (name "unconnected-(IC2-Pad5)") (class "Default")
      (node (ref "IC2") (pin "5") (pinfunction "5_5") (pintype "passive"))
    )
    (net (code "71") (name "unconnected-(IC3-ANALOG_0-Pad23)") (class "Default")
      (node (ref "IC3") (pin "23") (pinfunction "ANALOG_0_23") (pintype "bidirectional"))
    )
    (net (code "72") (name "unconnected-(IC3-ANALOG_1-Pad24)") (class "Default")
      (node (ref "IC3") (pin "24") (pinfunction "ANALOG_1_24") (pintype "bidirectional"))
    )
    (net (code "73") (name "unconnected-(IC3-ANALOG_2-Pad25)") (class "Default")
      (node (ref "IC3") (pin "25") (pinfunction "ANALOG_2_25") (pintype "bidirectional"))
    )
    (net (code "74") (name "unconnected-(IC3-ANALOG_3-Pad26)") (class "Default")
      (node (ref "IC3") (pin "26") (pinfunction "ANALOG_3_26") (pintype "bidirectional"))
    )
    (net (code "75") (name "unconnected-(IC3-ANALOG_4-Pad27)") (class "Default")
      (node (ref "IC3") (pin "27") (pinfunction "ANALOG_4_27") (pintype "bidirectional"))
    )
    (net (code "76") (name "unconnected-(IC3-ANALOG_5-Pad28)") (class "Default")
      (node (ref "IC3") (pin "28") (pinfunction "ANALOG_5_28") (pintype "bidirectional"))
    )
    (net (code "77") (name "unconnected-(IC3-ANALOG_REFERENCE-Pad21)") (class "Default")
      (node (ref "IC3") (pin "21") (pinfunction "ANALOG_REFERENCE_21") (pintype "passive"))
    )
    (net (code "78") (name "unconnected-(IC3-DIGITAL_0(RX)-Pad2)") (class "Default")
      (node (ref "IC3") (pin "2") (pinfunction "DIGITAL_0(RX)_2") (pintype "bidirectional"))
    )
    (net (code "79") (name "unconnected-(IC3-DIGITAL_1(TX)-Pad3)") (class "Default")
      (node (ref "IC3") (pin "3") (pinfunction "DIGITAL_1(TX)_3") (pintype "bidirectional"))
    )
    (net (code "80") (name "unconnected-(IC3-DIGITAL_10(PWM)-Pad16)") (class "Default")
      (node (ref "IC3") (pin "16") (pinfunction "DIGITAL_10(PWM)_16") (pintype "bidirectional"))
    )
    (net (code "81") (name "unconnected-(IC3-DIGITAL_11(PWM)-Pad17)") (class "Default")
      (node (ref "IC3") (pin "17") (pinfunction "DIGITAL_11(PWM)_17") (pintype "bidirectional"))
    )
    (net (code "82") (name "unconnected-(IC3-DIGITAL_12-Pad18)") (class "Default")
      (node (ref "IC3") (pin "18") (pinfunction "DIGITAL_12_18") (pintype "bidirectional"))
    )
    (net (code "83") (name "unconnected-(IC3-DIGITAL_13-Pad19)") (class "Default")
      (node (ref "IC3") (pin "19") (pinfunction "DIGITAL_13_19") (pintype "bidirectional"))
    )
    (net (code "84") (name "unconnected-(K2B-P-PadP@)") (class "Default")
      (node (ref "K2") (pin "P@") (pinfunction "P_P@") (pintype "passive"))
    )
    (net (code "85") (name "unconnected-(RELAYFTHORIOU-PadO)") (class "Default")
      (node (ref "RELAYFTHORIOU") (pin "O") (pinfunction "O_O") (pintype "passive"))
    )
    (net (code "86") (name "unconnected-(RELAYMESANYXTA-PadO)") (class "Default")
      (node (ref "RELAYMESANYXTA") (pin "O") (pinfunction "O_O") (pintype "passive"))
    )
    (net (code "87") (name "unconnected-(X1I-S-Pad8)") (class "Default")
      (node (ref "X1") (pin "8") (pinfunction "S_8") (pintype "passive"))
    )
    (net (code "88") (name "unconnected-(X1J-S-Pad9)") (class "Default")
      (node (ref "X1") (pin "9") (pinfunction "S_9") (pintype "passive"))
    )
  )
)
